# 6_uart_esc_i2c.net
KiCad netlist of a schematic drawn in Altium Designer
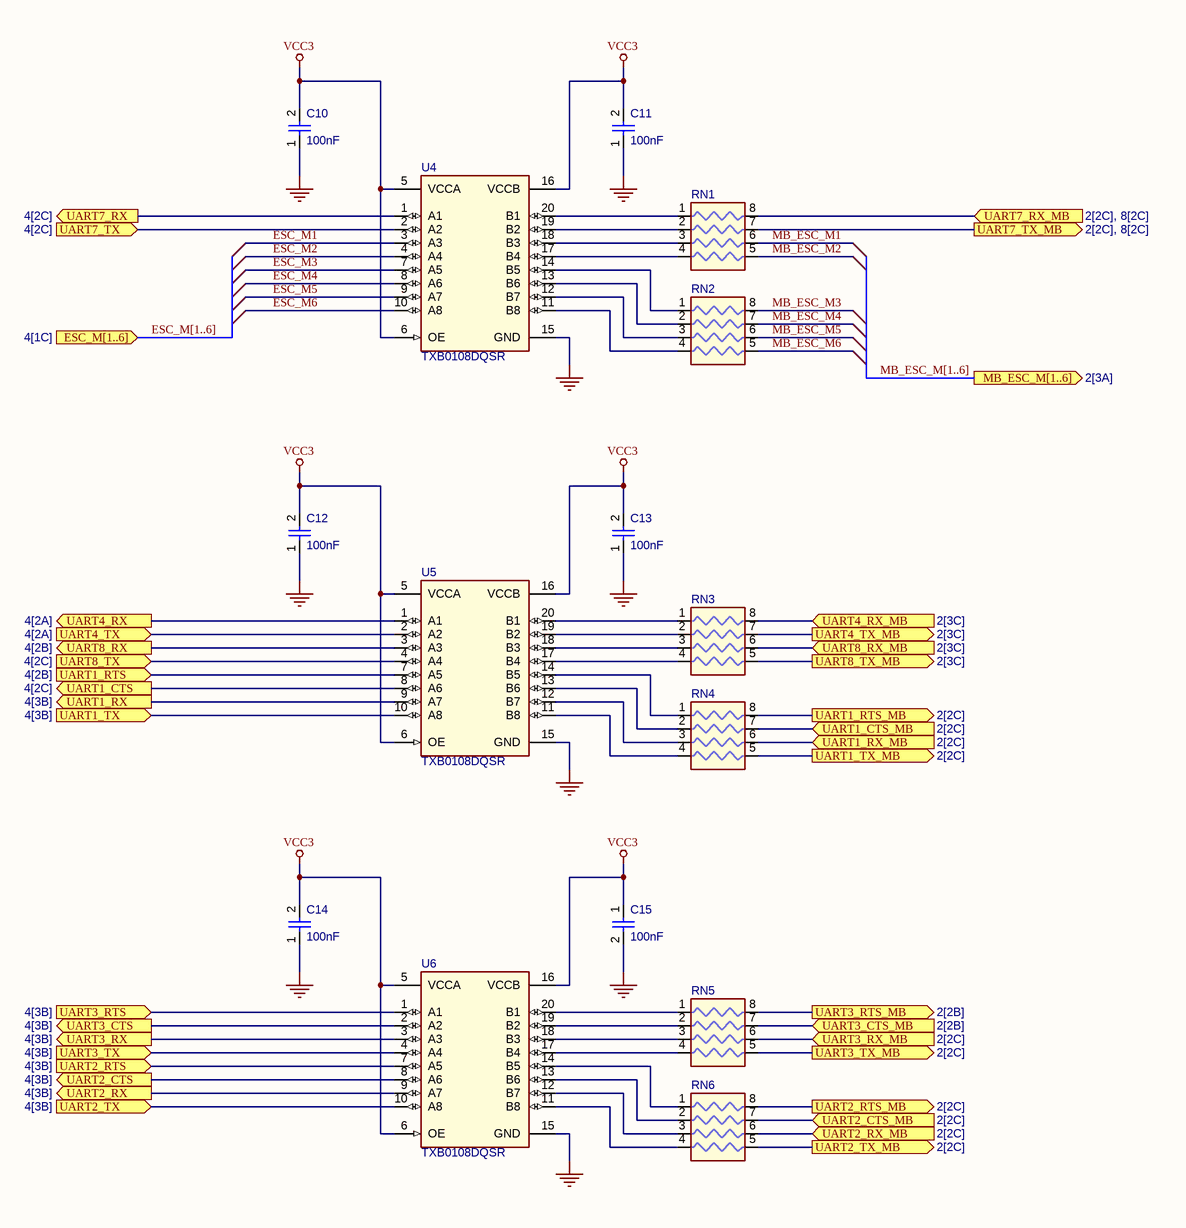
[diagram p0: 6_uart_esc_i2c.SchDoc]

(export (version "E")
  (design (tool "Eeschema 10.0.6"))
  (components
    (comp (ref "C10")
      (value "100nF")
      (footprint "CAPC0402(1005)60_L")
      (description "Chip Capacitor, 100nF +/-20%, 10V, 0402, Thickness 0.6 mm")
      (fields (field (name "TOLERANCE") "20%") (field (name "Comment") "Capacitor 100nF +/-20% 10V 0402"))
      (libsource (lib "<Company> Server") (part "CAP-NP-2"))
    )
    (comp (ref "C11")
      (value "100nF")
      (footprint "CAPC0402(1005)60_L")
      (description "Chip Capacitor, 100nF +/-20%, 10V, 0402, Thickness 0.6 mm")
      (fields (field (name "TOLERANCE") "20%") (field (name "Comment") "Capacitor 100nF +/-20% 10V 0402"))
      (libsource (lib "<Company> Server") (part "CAP-NP-2"))
    )
    (comp (ref "C12")
      (value "100nF")
      (footprint "CAPC0402(1005)60_L")
      (description "Chip Capacitor, 100nF +/-20%, 10V, 0402, Thickness 0.6 mm")
      (fields (field (name "TOLERANCE") "20%") (field (name "Comment") "Capacitor 100nF +/-20% 10V 0402"))
      (libsource (lib "<Company> Server") (part "CAP-NP-2"))
    )
    (comp (ref "C13")
      (value "100nF")
      (footprint "CAPC0402(1005)60_L")
      (description "Chip Capacitor, 100nF +/-20%, 10V, 0402, Thickness 0.6 mm")
      (fields (field (name "TOLERANCE") "20%") (field (name "Comment") "Capacitor 100nF +/-20% 10V 0402"))
      (libsource (lib "<Company> Server") (part "CAP-NP-2"))
    )
    (comp (ref "C14")
      (value "100nF")
      (footprint "CAPC0402(1005)60_L")
      (description "Chip Capacitor, 100nF +/-20%, 10V, 0402, Thickness 0.6 mm")
      (fields (field (name "TOLERANCE") "20%") (field (name "Comment") "Capacitor 100nF +/-20% 10V 0402"))
      (libsource (lib "<Company> Server") (part "CAP-NP-2"))
    )
    (comp (ref "C15")
      (value "100nF")
      (footprint "CAPC0402(1005)60_L")
      (description "Chip Capacitor, 100nF +/-20%, 10V, 0402, Thickness 0.6 mm")
      (fields (field (name "TOLERANCE") "20%") (field (name "Comment") "Capacitor 100nF +/-20% 10V 0402"))
      (libsource (lib "<Company> Server") (part "CAP-NP-2"))
    )
    (comp (ref "RN1")
      (value "Resistor 200R +/-5% 0402 62.5 mW")
      (footprint "Panasonic_EXB28")
      (fields (field (name "TOLERANCE") "5%") (field (name "POWER") "62.5mW"))
      (libsource (lib "<Company> Server") (part "RES-P-4"))
    )
    (comp (ref "RN2")
      (value "Resistor 200R +/-5% 0402 62.5 mW")
      (footprint "Panasonic_EXB28")
      (fields (field (name "TOLERANCE") "5%") (field (name "POWER") "62.5mW"))
      (libsource (lib "<Company> Server") (part "RES-P-4"))
    )
    (comp (ref "RN3")
      (value "Resistor 200R +/-5% 0402 62.5 mW")
      (footprint "Panasonic_EXB28")
      (fields (field (name "TOLERANCE") "5%") (field (name "POWER") "62.5mW"))
      (libsource (lib "<Company> Server") (part "RES-P-4"))
    )
    (comp (ref "RN4")
      (value "Resistor 200R +/-5% 0402 62.5 mW")
      (footprint "Panasonic_EXB28")
      (fields (field (name "TOLERANCE") "5%") (field (name "POWER") "62.5mW"))
      (libsource (lib "<Company> Server") (part "RES-P-4"))
    )
    (comp (ref "RN5")
      (value "Resistor 200R +/-5% 0402 62.5 mW")
      (footprint "Panasonic_EXB28")
      (fields (field (name "TOLERANCE") "5%") (field (name "POWER") "62.5mW"))
      (libsource (lib "<Company> Server") (part "RES-P-4"))
    )
    (comp (ref "RN6")
      (value "Resistor 200R +/-5% 0402 62.5 mW")
      (footprint "Panasonic_EXB28")
      (fields (field (name "TOLERANCE") "5%") (field (name "POWER") "62.5mW"))
      (libsource (lib "<Company> Server") (part "RES-P-4"))
    )
    (comp (ref "U4")
      (value "TXB0108DQSR")
      (footprint "DQS0020A_V")
      (libsource (lib "<Company> Server") (part "CMP-00162-7"))
    )
    (comp (ref "U5")
      (value "TXB0108DQSR")
      (footprint "DQS0020A_V")
      (libsource (lib "<Company> Server") (part "CMP-00162-7"))
    )
    (comp (ref "U6")
      (value "TXB0108DQSR")
      (footprint "DQS0020A_V")
      (libsource (lib "<Company> Server") (part "CMP-00162-7"))
    )
  )
  (nets
    (net (code "1") (name "/ESC_M1") (class "Default")
      (node (ref "U4") (pin "3") (pinfunction "A3_3") (pintype "bidirectional"))
    )
    (net (code "2") (name "/ESC_M2") (class "Default")
      (node (ref "U4") (pin "4") (pinfunction "A4_4") (pintype "bidirectional"))
    )
    (net (code "3") (name "/ESC_M3") (class "Default")
      (node (ref "U4") (pin "7") (pinfunction "A5_7") (pintype "bidirectional"))
    )
    (net (code "4") (name "/ESC_M4") (class "Default")
      (node (ref "U4") (pin "8") (pinfunction "A6_8") (pintype "bidirectional"))
    )
    (net (code "5") (name "/ESC_M5") (class "Default")
      (node (ref "U4") (pin "9") (pinfunction "A7_9") (pintype "bidirectional"))
    )
    (net (code "6") (name "/ESC_M6") (class "Default")
      (node (ref "U4") (pin "10") (pinfunction "A8_10") (pintype "bidirectional"))
    )
    (net (code "8") (name "/MB_ESC_M1") (class "Default")
      (node (ref "RN1") (pin "6") (pinfunction "2_6") (pintype "passive"))
    )
    (net (code "9") (name "/MB_ESC_M2") (class "Default")
      (node (ref "RN1") (pin "5") (pinfunction "2_5") (pintype "passive"))
    )
    (net (code "10") (name "/MB_ESC_M3") (class "Default")
      (node (ref "RN2") (pin "8") (pinfunction "2_8") (pintype "passive"))
    )
    (net (code "11") (name "/MB_ESC_M4") (class "Default")
      (node (ref "RN2") (pin "7") (pinfunction "2_7") (pintype "passive"))
    )
    (net (code "12") (name "/MB_ESC_M5") (class "Default")
      (node (ref "RN2") (pin "6") (pinfunction "2_6") (pintype "passive"))
    )
    (net (code "13") (name "/MB_ESC_M6") (class "Default")
      (node (ref "RN2") (pin "5") (pinfunction "2_5") (pintype "passive"))
    )
    (net (code "15") (name "/UART1_CTS") (class "Default")
      (node (ref "U5") (pin "8") (pinfunction "A6_8") (pintype "bidirectional"))
    )
    (net (code "16") (name "/UART1_CTS_MB") (class "Default")
      (node (ref "RN4") (pin "7") (pinfunction "2_7") (pintype "passive"))
    )
    (net (code "17") (name "/UART1_RTS") (class "Default")
      (node (ref "U5") (pin "7") (pinfunction "A5_7") (pintype "bidirectional"))
    )
    (net (code "18") (name "/UART1_RTS_MB") (class "Default")
      (node (ref "RN4") (pin "8") (pinfunction "2_8") (pintype "passive"))
    )
    (net (code "19") (name "/UART1_RX") (class "Default")
      (node (ref "U5") (pin "9") (pinfunction "A7_9") (pintype "bidirectional"))
    )
    (net (code "20") (name "/UART1_RX_MB") (class "Default")
      (node (ref "RN4") (pin "6") (pinfunction "2_6") (pintype "passive"))
    )
    (net (code "21") (name "/UART1_TX") (class "Default")
      (node (ref "U5") (pin "10") (pinfunction "A8_10") (pintype "bidirectional"))
    )
    (net (code "22") (name "/UART1_TX_MB") (class "Default")
      (node (ref "RN4") (pin "5") (pinfunction "2_5") (pintype "passive"))
    )
    (net (code "23") (name "/UART2_CTS") (class "Default")
      (node (ref "U6") (pin "8") (pinfunction "A6_8") (pintype "bidirectional"))
    )
    (net (code "24") (name "/UART2_CTS_MB") (class "Default")
      (node (ref "RN6") (pin "7") (pinfunction "2_7") (pintype "passive"))
    )
    (net (code "25") (name "/UART2_RTS") (class "Default")
      (node (ref "U6") (pin "7") (pinfunction "A5_7") (pintype "bidirectional"))
    )
    (net (code "26") (name "/UART2_RTS_MB") (class "Default")
      (node (ref "RN6") (pin "8") (pinfunction "2_8") (pintype "passive"))
    )
    (net (code "27") (name "/UART2_RX") (class "Default")
      (node (ref "U6") (pin "9") (pinfunction "A7_9") (pintype "bidirectional"))
    )
    (net (code "28") (name "/UART2_RX_MB") (class "Default")
      (node (ref "RN6") (pin "6") (pinfunction "2_6") (pintype "passive"))
    )
    (net (code "29") (name "/UART2_TX") (class "Default")
      (node (ref "U6") (pin "10") (pinfunction "A8_10") (pintype "bidirectional"))
    )
    (net (code "30") (name "/UART2_TX_MB") (class "Default")
      (node (ref "RN6") (pin "5") (pinfunction "2_5") (pintype "passive"))
    )
    (net (code "31") (name "/UART3_CTS") (class "Default")
      (node (ref "U6") (pin "2") (pinfunction "A2_2") (pintype "bidirectional"))
    )
    (net (code "32") (name "/UART3_CTS_MB") (class "Default")
      (node (ref "RN5") (pin "7") (pinfunction "2_7") (pintype "passive"))
    )
    (net (code "33") (name "/UART3_RTS") (class "Default")
      (node (ref "U6") (pin "1") (pinfunction "A1_1") (pintype "bidirectional"))
    )
    (net (code "34") (name "/UART3_RTS_MB") (class "Default")
      (node (ref "RN5") (pin "8") (pinfunction "2_8") (pintype "passive"))
    )
    (net (code "35") (name "/UART3_RX") (class "Default")
      (node (ref "U6") (pin "3") (pinfunction "A3_3") (pintype "bidirectional"))
    )
    (net (code "36") (name "/UART3_RX_MB") (class "Default")
      (node (ref "RN5") (pin "6") (pinfunction "2_6") (pintype "passive"))
    )
    (net (code "37") (name "/UART3_TX") (class "Default")
      (node (ref "U6") (pin "4") (pinfunction "A4_4") (pintype "bidirectional"))
    )
    (net (code "38") (name "/UART3_TX_MB") (class "Default")
      (node (ref "RN5") (pin "5") (pinfunction "2_5") (pintype "passive"))
    )
    (net (code "39") (name "/UART4_RX") (class "Default")
      (node (ref "U5") (pin "1") (pinfunction "A1_1") (pintype "bidirectional"))
    )
    (net (code "40") (name "/UART4_RX_MB") (class "Default")
      (node (ref "RN3") (pin "8") (pinfunction "2_8") (pintype "passive"))
    )
    (net (code "41") (name "/UART4_TX") (class "Default")
      (node (ref "U5") (pin "2") (pinfunction "A2_2") (pintype "bidirectional"))
    )
    (net (code "42") (name "/UART4_TX_MB") (class "Default")
      (node (ref "RN3") (pin "7") (pinfunction "2_7") (pintype "passive"))
    )
    (net (code "43") (name "/UART7_RX") (class "Default")
      (node (ref "U4") (pin "1") (pinfunction "A1_1") (pintype "bidirectional"))
    )
    (net (code "44") (name "/UART7_RX_MB") (class "Default")
      (node (ref "RN1") (pin "8") (pinfunction "2_8") (pintype "passive"))
    )
    (net (code "45") (name "/UART7_TX") (class "Default")
      (node (ref "U4") (pin "2") (pinfunction "A2_2") (pintype "bidirectional"))
    )
    (net (code "46") (name "/UART7_TX_MB") (class "Default")
      (node (ref "RN1") (pin "7") (pinfunction "2_7") (pintype "passive"))
    )
    (net (code "47") (name "/UART8_RX") (class "Default")
      (node (ref "U5") (pin "3") (pinfunction "A3_3") (pintype "bidirectional"))
    )
    (net (code "48") (name "/UART8_RX_MB") (class "Default")
      (node (ref "RN3") (pin "6") (pinfunction "2_6") (pintype "passive"))
    )
    (net (code "49") (name "/UART8_TX") (class "Default")
      (node (ref "U5") (pin "4") (pinfunction "A4_4") (pintype "bidirectional"))
    )
    (net (code "50") (name "/UART8_TX_MB") (class "Default")
      (node (ref "RN3") (pin "5") (pinfunction "2_5") (pintype "passive"))
    )
    (net (code "51") (name "GND") (class "Default")
      (node (ref "C10") (pin "1") (pinfunction "1_1") (pintype "passive"))
      (node (ref "C11") (pin "1") (pinfunction "1_1") (pintype "passive"))
      (node (ref "C12") (pin "1") (pinfunction "1_1") (pintype "passive"))
      (node (ref "C13") (pin "1") (pinfunction "1_1") (pintype "passive"))
      (node (ref "C14") (pin "1") (pinfunction "1_1") (pintype "passive"))
      (node (ref "C15") (pin "2") (pinfunction "2_2") (pintype "passive"))
      (node (ref "U4") (pin "15") (pinfunction "GND_15") (pintype "power_in"))
      (node (ref "U5") (pin "15") (pinfunction "GND_15") (pintype "power_in"))
      (node (ref "U6") (pin "15") (pinfunction "GND_15") (pintype "power_in"))
    )
    (net (code "52") (name "Net-(U4-B1)") (class "Default")
      (node (ref "RN1") (pin "1") (pinfunction "1_1") (pintype "passive"))
      (node (ref "U4") (pin "20") (pinfunction "B1_20") (pintype "bidirectional"))
    )
    (net (code "53") (name "Net-(U4-B2)") (class "Default")
      (node (ref "RN1") (pin "2") (pinfunction "1_2") (pintype "passive"))
      (node (ref "U4") (pin "19") (pinfunction "B2_19") (pintype "bidirectional"))
    )
    (net (code "54") (name "Net-(U4-B3)") (class "Default")
      (node (ref "RN1") (pin "3") (pinfunction "1_3") (pintype "passive"))
      (node (ref "U4") (pin "18") (pinfunction "B3_18") (pintype "bidirectional"))
    )
    (net (code "55") (name "Net-(U4-B4)") (class "Default")
      (node (ref "RN1") (pin "4") (pinfunction "1_4") (pintype "passive"))
      (node (ref "U4") (pin "17") (pinfunction "B4_17") (pintype "bidirectional"))
    )
    (net (code "56") (name "Net-(U4-B5)") (class "Default")
      (node (ref "RN2") (pin "1") (pinfunction "1_1") (pintype "passive"))
      (node (ref "U4") (pin "14") (pinfunction "B5_14") (pintype "bidirectional"))
    )
    (net (code "57") (name "Net-(U4-B6)") (class "Default")
      (node (ref "RN2") (pin "2") (pinfunction "1_2") (pintype "passive"))
      (node (ref "U4") (pin "13") (pinfunction "B6_13") (pintype "bidirectional"))
    )
    (net (code "58") (name "Net-(U4-B7)") (class "Default")
      (node (ref "RN2") (pin "3") (pinfunction "1_3") (pintype "passive"))
      (node (ref "U4") (pin "12") (pinfunction "B7_12") (pintype "bidirectional"))
    )
    (net (code "59") (name "Net-(U4-B8)") (class "Default")
      (node (ref "RN2") (pin "4") (pinfunction "1_4") (pintype "passive"))
      (node (ref "U4") (pin "11") (pinfunction "B8_11") (pintype "bidirectional"))
    )
    (net (code "60") (name "Net-(U5-B1)") (class "Default")
      (node (ref "RN3") (pin "1") (pinfunction "1_1") (pintype "passive"))
      (node (ref "U5") (pin "20") (pinfunction "B1_20") (pintype "bidirectional"))
    )
    (net (code "61") (name "Net-(U5-B2)") (class "Default")
      (node (ref "RN3") (pin "2") (pinfunction "1_2") (pintype "passive"))
      (node (ref "U5") (pin "19") (pinfunction "B2_19") (pintype "bidirectional"))
    )
    (net (code "62") (name "Net-(U5-B3)") (class "Default")
      (node (ref "RN3") (pin "3") (pinfunction "1_3") (pintype "passive"))
      (node (ref "U5") (pin "18") (pinfunction "B3_18") (pintype "bidirectional"))
    )
    (net (code "63") (name "Net-(U5-B4)") (class "Default")
      (node (ref "RN3") (pin "4") (pinfunction "1_4") (pintype "passive"))
      (node (ref "U5") (pin "17") (pinfunction "B4_17") (pintype "bidirectional"))
    )
    (net (code "64") (name "Net-(U5-B5)") (class "Default")
      (node (ref "RN4") (pin "1") (pinfunction "1_1") (pintype "passive"))
      (node (ref "U5") (pin "14") (pinfunction "B5_14") (pintype "bidirectional"))
    )
    (net (code "65") (name "Net-(U5-B6)") (class "Default")
      (node (ref "RN4") (pin "2") (pinfunction "1_2") (pintype "passive"))
      (node (ref "U5") (pin "13") (pinfunction "B6_13") (pintype "bidirectional"))
    )
    (net (code "66") (name "Net-(U5-B7)") (class "Default")
      (node (ref "RN4") (pin "3") (pinfunction "1_3") (pintype "passive"))
      (node (ref "U5") (pin "12") (pinfunction "B7_12") (pintype "bidirectional"))
    )
    (net (code "67") (name "Net-(U5-B8)") (class "Default")
      (node (ref "RN4") (pin "4") (pinfunction "1_4") (pintype "passive"))
      (node (ref "U5") (pin "11") (pinfunction "B8_11") (pintype "bidirectional"))
    )
    (net (code "68") (name "Net-(U6-B1)") (class "Default")
      (node (ref "RN5") (pin "1") (pinfunction "1_1") (pintype "passive"))
      (node (ref "U6") (pin "20") (pinfunction "B1_20") (pintype "bidirectional"))
    )
    (net (code "69") (name "Net-(U6-B2)") (class "Default")
      (node (ref "RN5") (pin "2") (pinfunction "1_2") (pintype "passive"))
      (node (ref "U6") (pin "19") (pinfunction "B2_19") (pintype "bidirectional"))
    )
    (net (code "70") (name "Net-(U6-B3)") (class "Default")
      (node (ref "RN5") (pin "3") (pinfunction "1_3") (pintype "passive"))
      (node (ref "U6") (pin "18") (pinfunction "B3_18") (pintype "bidirectional"))
    )
    (net (code "71") (name "Net-(U6-B4)") (class "Default")
      (node (ref "RN5") (pin "4") (pinfunction "1_4") (pintype "passive"))
      (node (ref "U6") (pin "17") (pinfunction "B4_17") (pintype "bidirectional"))
    )
    (net (code "72") (name "Net-(U6-B5)") (class "Default")
      (node (ref "RN6") (pin "1") (pinfunction "1_1") (pintype "passive"))
      (node (ref "U6") (pin "14") (pinfunction "B5_14") (pintype "bidirectional"))
    )
    (net (code "73") (name "Net-(U6-B6)") (class "Default")
      (node (ref "RN6") (pin "2") (pinfunction "1_2") (pintype "passive"))
      (node (ref "U6") (pin "13") (pinfunction "B6_13") (pintype "bidirectional"))
    )
    (net (code "74") (name "Net-(U6-B7)") (class "Default")
      (node (ref "RN6") (pin "3") (pinfunction "1_3") (pintype "passive"))
      (node (ref "U6") (pin "12") (pinfunction "B7_12") (pintype "bidirectional"))
    )
    (net (code "75") (name "Net-(U6-B8)") (class "Default")
      (node (ref "RN6") (pin "4") (pinfunction "1_4") (pintype "passive"))
      (node (ref "U6") (pin "11") (pinfunction "B8_11") (pintype "bidirectional"))
    )
    (net (code "76") (name "VCC3") (class "Default")
      (node (ref "C10") (pin "2") (pinfunction "2_2") (pintype "passive"))
      (node (ref "C11") (pin "2") (pinfunction "2_2") (pintype "passive"))
      (node (ref "C12") (pin "2") (pinfunction "2_2") (pintype "passive"))
      (node (ref "C13") (pin "2") (pinfunction "2_2") (pintype "passive"))
      (node (ref "C14") (pin "2") (pinfunction "2_2") (pintype "passive"))
      (node (ref "C15") (pin "1") (pinfunction "1_1") (pintype "passive"))
      (node (ref "U4") (pin "16") (pinfunction "VCCB_16") (pintype "power_in"))
      (node (ref "U4") (pin "5") (pinfunction "VCCA_5") (pintype "power_in"))
      (node (ref "U4") (pin "6") (pinfunction "OE_6") (pintype "input"))
      (node (ref "U5") (pin "16") (pinfunction "VCCB_16") (pintype "power_in"))
      (node (ref "U5") (pin "5") (pinfunction "VCCA_5") (pintype "power_in"))
      (node (ref "U5") (pin "6") (pinfunction "OE_6") (pintype "input"))
      (node (ref "U6") (pin "16") (pinfunction "VCCB_16") (pintype "power_in"))
      (node (ref "U6") (pin "5") (pinfunction "VCCA_5") (pintype "power_in"))
      (node (ref "U6") (pin "6") (pinfunction "OE_6") (pintype "input"))
    )
  )
)
